# 2_Smoke_detector.net
KiCad netlist of a schematic drawn in Altium Designer
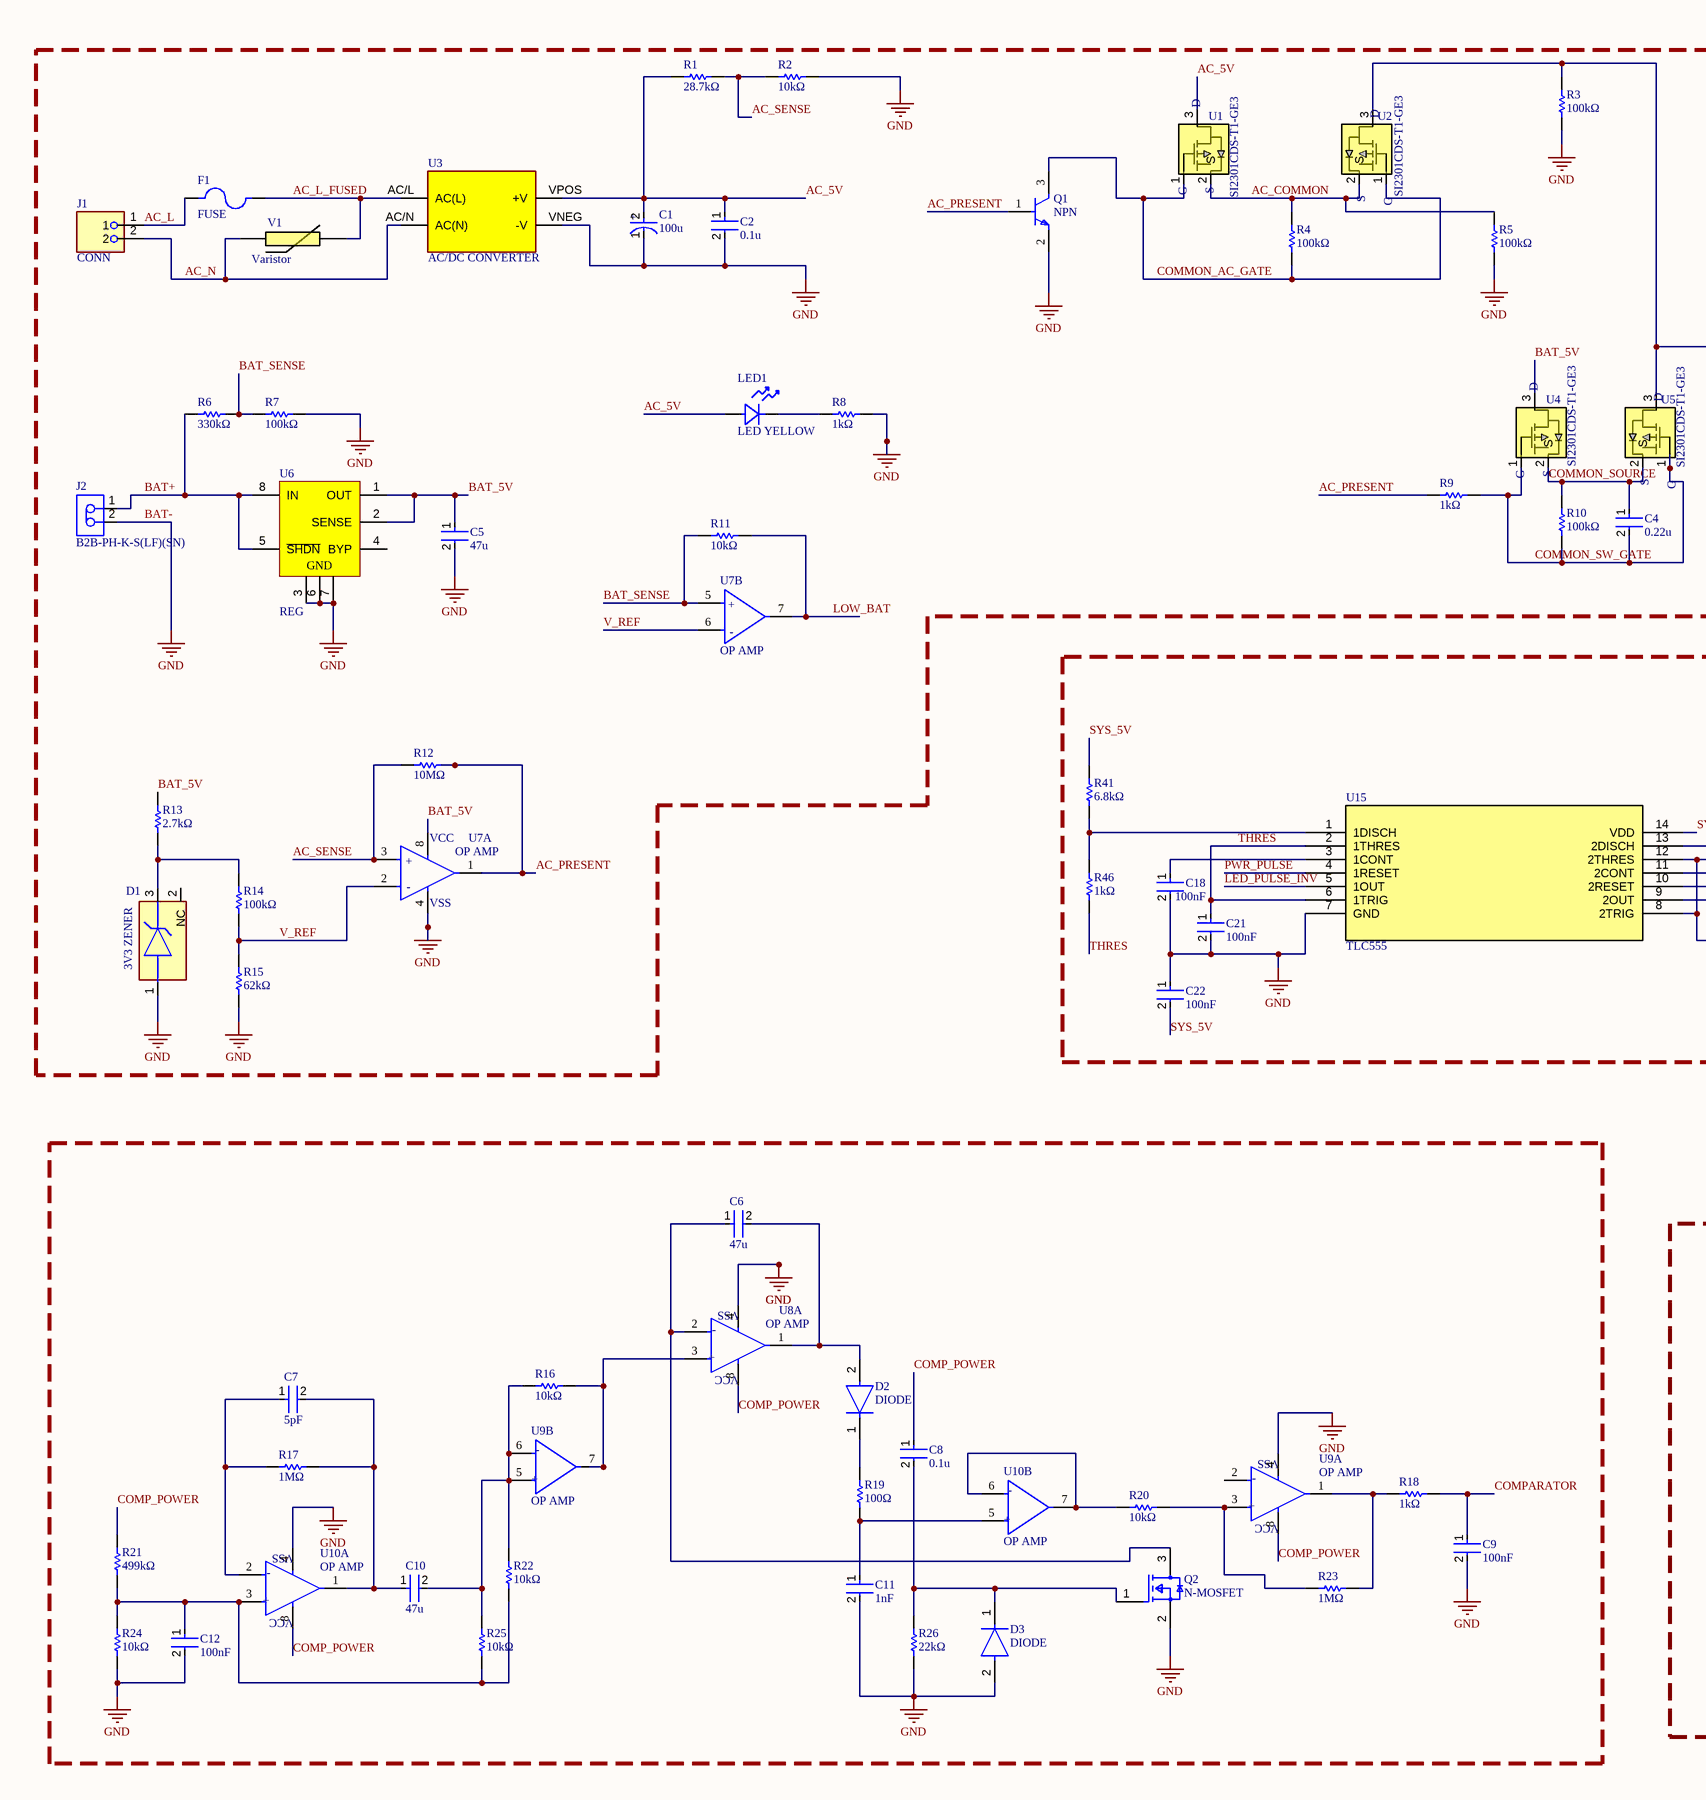
[diagram p0: 2_Smoke_detector.SchDoc, left]
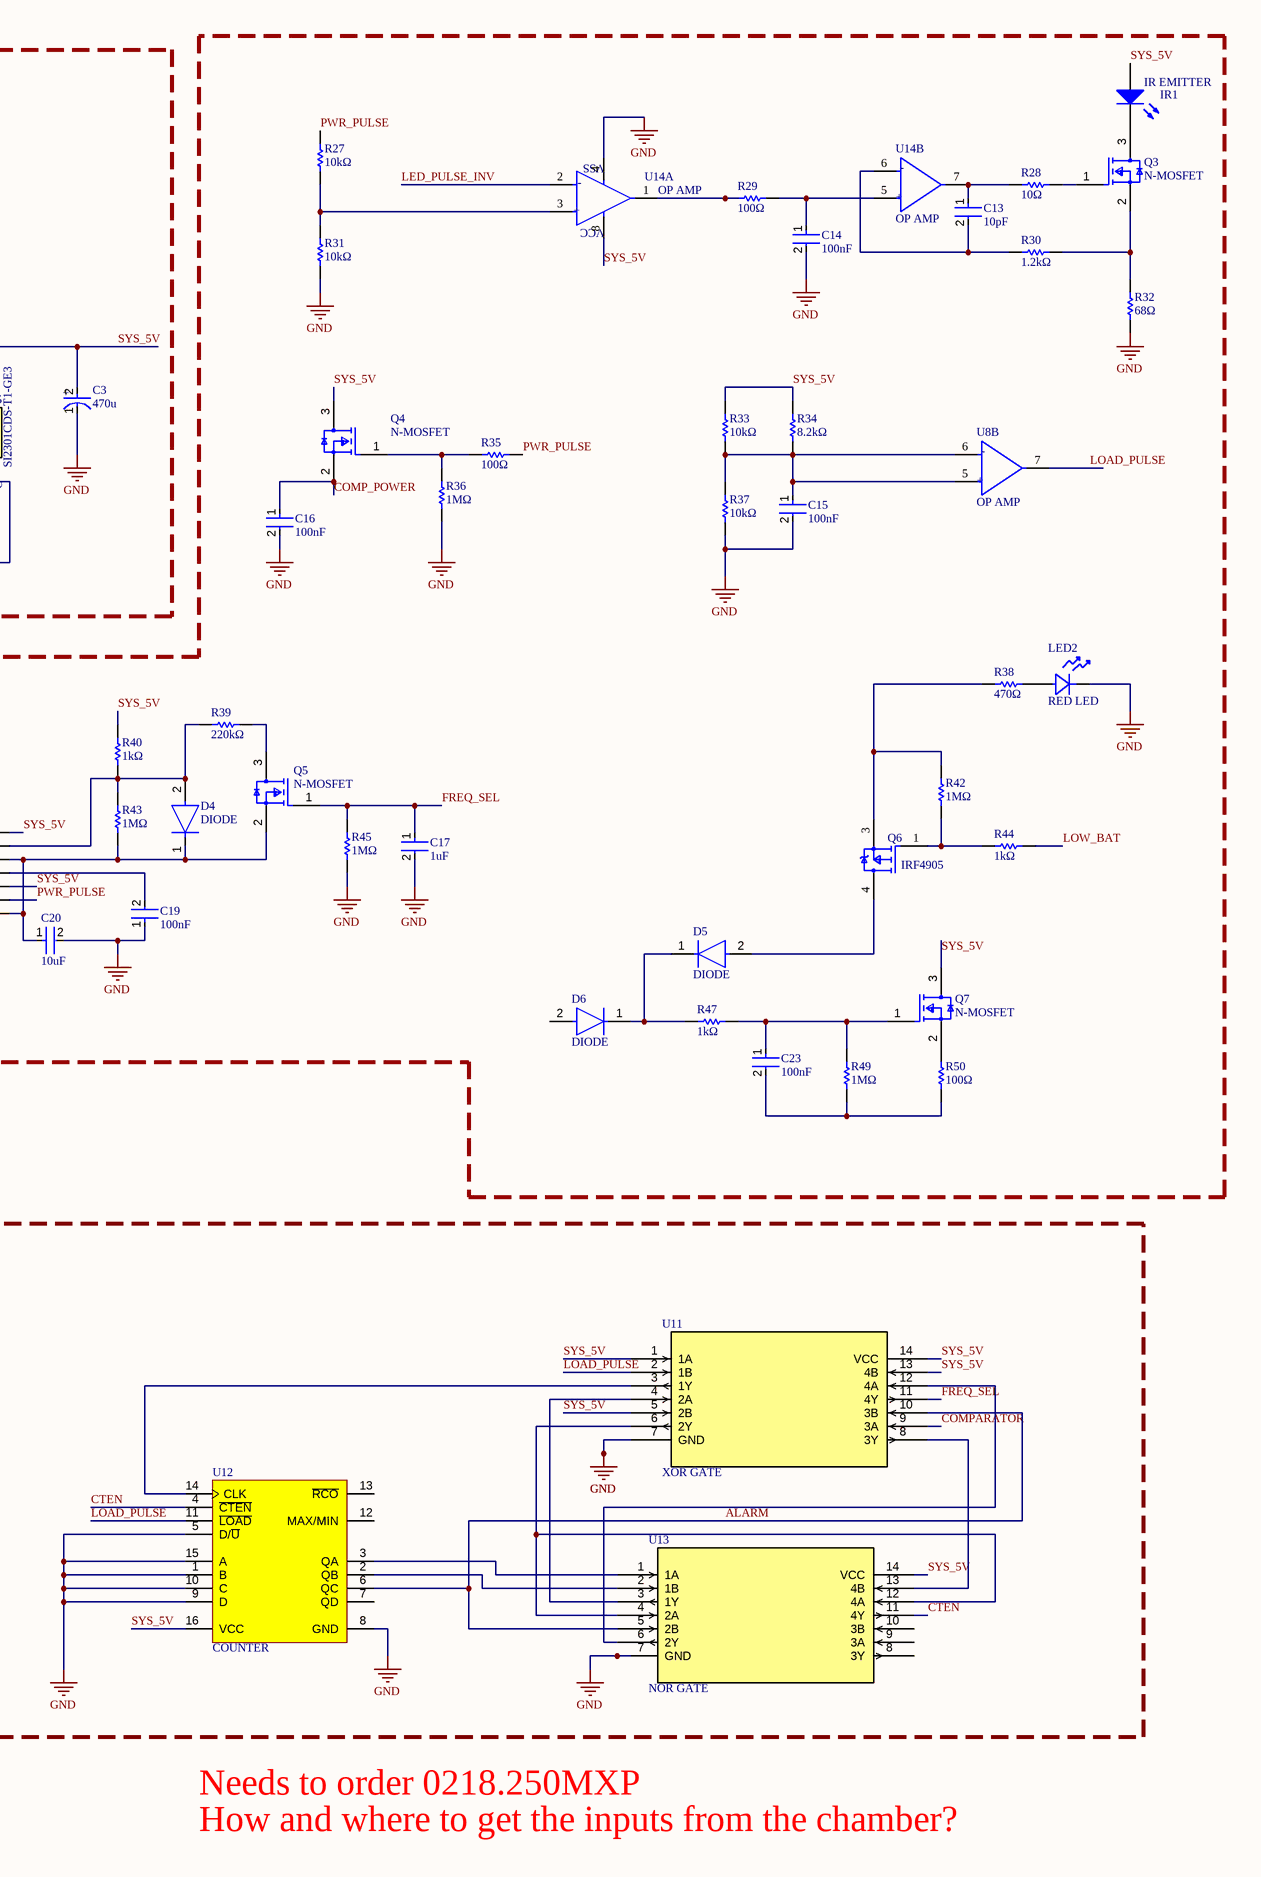
[diagram p1: 2_Smoke_detector.SchDoc, right]

(export (version "E")
  (design (tool "Eeschema 10.0.6"))
  (components
    (comp (ref "C1")
      (value "100u")
      (footprint "CAP_100u")
      (description "CAP ALUM 100uF 20% 16V SMD")
      (fields (field (name "TOLERANCE") "20%") (field (name "VOLTAGE") "16V"))
      (libsource (lib "2_Smoke_Detector") (part "EEEFT1C101AR"))
    )
    (comp (ref "C2")
      (value "0.1u")
      (footprint "0805_CER_CAP")
      (description "CAP CER 0.1uF 50V X7R 0805")
      (fields (field (name "TOLERANCE") "10%") (field (name "VOLTAGE") "50V"))
      (libsource (lib "2_Smoke_Detector") (part "CL21B104KBCNNNC"))
    )
    (comp (ref "C3")
      (value "470u")
      (footprint "Radial_SMD_CAP")
      (description "CAP ALUM 470uF ±20% 10V SMD")
      (fields
        (field (name "MANUFACTURER") "Panasonic")
        (field (name "MANUFACTURER PART NUMBER") "EEEFK1A471P")
      )
      (libsource (lib "2_Smoke_Detector") (part "EEEFK1A471P"))
    )
    (comp (ref "C4")
      (value "0.22u")
      (footprint "0805_CER_CAP")
      (description "CAP CER 0.22uF 10V X7R 0805")
      (fields
        (field (name "MANUFACTURER") "Yageo Group")
        (field (name "MANUFACTURER PART NUMBER") "CC0805KRX7R6BB224")
      )
      (libsource (lib "2_Smoke_Detector") (part "CC0805KRX7R6BB224"))
    )
    (comp (ref "C5")
      (value "47u")
      (footprint "0805_CER_CAP")
      (description "CAP CER 47uF 10V X5R 0805")
      (fields
        (field (name "MANUFACTURER") "Murata")
        (field (name "MANUFACTURER PART NUMBER") "GRM21BR61A476ME15L")
      )
      (libsource (lib "2_Smoke_Detector") (part "GRM21BR61A476ME15L"))
    )
    (comp (ref "C6")
      (value "47u")
      (footprint "0805_CER_CAP")
      (description "CAP CER 47uF 10V X5R 0805")
      (fields
        (field (name "MANUFACTURER") "Murata")
        (field (name "MANUFACTURER PART NUMBER") "GRM21BR61A476ME15L")
      )
      (libsource (lib "2_Smoke_Detector") (part "GRM21BR61A476ME15L"))
    )
    (comp (ref "C7")
      (value "5pF")
      (footprint "0805_CER_CAP")
      (description "CAP CER 5pF 50V NP0 0805")
      (fields
        (field (name "MANUFACTURER") "Yageo Group")
        (field (name "MANUFACTURER PART NUMBER") "CC0805CRNPO9BN5R0")
      )
      (libsource (lib "2_Smoke_Detector") (part "CC0805CRNPO9BN5R0"))
    )
    (comp (ref "C8")
      (value "0.1u")
      (footprint "0805_CER_CAP")
      (description "CAP CER 0.1uF 50V X7R 0805")
      (fields (field (name "TOLERANCE") "10%") (field (name "VOLTAGE") "50V"))
      (libsource (lib "2_Smoke_Detector") (part "CL21B104KBCNNNC"))
    )
    (comp (ref "C9")
      (value "100nF")
      (footprint "0805_CER_CAP")
      (description "CAP CER 100nF 50V X7R 0805")
      (fields
        (field (name "MANUFACTURER") "Yageo Group")
        (field (name "MANUFACTURER PART NUMBER") "CC0805KRX7R9BB104")
      )
      (libsource (lib "2_Smoke_Detector") (part "CC0805KRX7R9BB104"))
    )
    (comp (ref "C10")
      (value "47u")
      (footprint "0805_CER_CAP")
      (description "CAP CER 47uF 10V X5R 0805")
      (fields
        (field (name "MANUFACTURER") "Murata")
        (field (name "MANUFACTURER PART NUMBER") "GRM21BR61A476ME15L")
      )
      (libsource (lib "2_Smoke_Detector") (part "GRM21BR61A476ME15L"))
    )
    (comp (ref "C11")
      (value "1nF")
      (footprint "0805_CER_CAP")
      (description "CAP CER 1nF 50V X7R 0805")
      (fields
        (field (name "MANUFACTURER") "Samsung Electro-Mechanics")
        (field (name "MANUFACTURER PART NUMBER") "CL21B102KBCNNNC")
      )
      (libsource (lib "2_Smoke_Detector") (part "CL21B102KBCNNNC"))
    )
    (comp (ref "C12")
      (value "100nF")
      (footprint "0805_CER_CAP")
      (description "CAP CER 100nF 50V X7R 0805")
      (fields
        (field (name "MANUFACTURER") "Yageo Group")
        (field (name "MANUFACTURER PART NUMBER") "CC0805KRX7R9BB104")
      )
      (libsource (lib "2_Smoke_Detector") (part "CC0805KRX7R9BB104"))
    )
    (comp (ref "C13")
      (value "10pF")
      (footprint "0805_CER_CAP")
      (description "CAP CER 10pF 50V NP0 0805")
      (fields
        (field (name "MANUFACTURER") "Yageo Group")
        (field (name "MANUFACTURER PART NUMBER") "CC0805JRNPO9BN100")
      )
      (libsource (lib "2_Smoke_Detector") (part "CC0805JRNPO9BN100"))
    )
    (comp (ref "C14")
      (value "100nF")
      (footprint "0805_CER_CAP")
      (description "CAP CER 100nF 50V X7R 0805")
      (fields
        (field (name "MANUFACTURER") "Yageo Group")
        (field (name "MANUFACTURER PART NUMBER") "CC0805KRX7R9BB104")
      )
      (libsource (lib "2_Smoke_Detector") (part "CC0805KRX7R9BB104"))
    )
    (comp (ref "C15")
      (value "100nF")
      (footprint "0805_CER_CAP")
      (description "CAP CER 100nF 50V X7R 0805")
      (fields
        (field (name "MANUFACTURER") "Yageo Group")
        (field (name "MANUFACTURER PART NUMBER") "CC0805KRX7R9BB104")
      )
      (libsource (lib "2_Smoke_Detector") (part "CC0805KRX7R9BB104"))
    )
    (comp (ref "C16")
      (value "100nF")
      (footprint "0805_CER_CAP")
      (description "CAP CER 100nF 50V X7R 0805")
      (fields
        (field (name "MANUFACTURER") "Yageo Group")
        (field (name "MANUFACTURER PART NUMBER") "CC0805KRX7R9BB104")
      )
      (libsource (lib "2_Smoke_Detector") (part "CC0805KRX7R9BB104"))
    )
    (comp (ref "C17")
      (value "1uF")
      (footprint "0805_CER_CAP")
      (description "CAP CER 1uF 50V X7R 0805")
      (fields
        (field (name "MANUFACTURER") "Samsung Electro-Mechanics")
        (field (name "MANUFACTURER PART NUMBER") "CL21B105KBFNNNE")
      )
      (libsource (lib "2_Smoke_Detector") (part "CL21B105KBFNNNE"))
    )
    (comp (ref "C18")
      (value "100nF")
      (footprint "0805_CER_CAP")
      (description "CAP CER 100nF 50V X7R 0805")
      (fields
        (field (name "MANUFACTURER") "Yageo Group")
        (field (name "MANUFACTURER PART NUMBER") "CC0805KRX7R9BB104")
      )
      (libsource (lib "2_Smoke_Detector") (part "CC0805KRX7R9BB104"))
    )
    (comp (ref "C19")
      (value "100nF")
      (footprint "0805_CER_CAP")
      (description "CAP CER 100nF 50V X7R 0805")
      (fields
        (field (name "MANUFACTURER") "Yageo Group")
        (field (name "MANUFACTURER PART NUMBER") "CC0805KRX7R9BB104")
      )
      (libsource (lib "2_Smoke_Detector") (part "CC0805KRX7R9BB104"))
    )
    (comp (ref "C20")
      (value "10uF")
      (footprint "0805_CER_CAP")
      (description "CAP CER 10uF 25V X5R 0805")
      (fields
        (field (name "MANUFACTURER") "TAIYO YUDEN")
        (field (name "MANUFACTURER PART NUMBER") "TMK212BBJ106KG-T")
      )
      (libsource (lib "2_Smoke_Detector") (part "TMK212BBJ106KG-T"))
    )
    (comp (ref "C21")
      (value "100nF")
      (footprint "0805_CER_CAP")
      (description "CAP CER 100nF 50V X7R 0805")
      (fields
        (field (name "MANUFACTURER") "Yageo Group")
        (field (name "MANUFACTURER PART NUMBER") "CC0805KRX7R9BB104")
      )
      (libsource (lib "2_Smoke_Detector") (part "CC0805KRX7R9BB104"))
    )
    (comp (ref "C22")
      (value "100nF")
      (footprint "0805_CER_CAP")
      (description "CAP CER 100nF 50V X7R 0805")
      (fields
        (field (name "MANUFACTURER") "Yageo Group")
        (field (name "MANUFACTURER PART NUMBER") "CC0805KRX7R9BB104")
      )
      (libsource (lib "2_Smoke_Detector") (part "CC0805KRX7R9BB104"))
    )
    (comp (ref "C23")
      (value "100nF")
      (footprint "0805_CER_CAP")
      (description "CAP CER 100nF 50V X7R 0805")
      (fields
        (field (name "MANUFACTURER") "Yageo Group")
        (field (name "MANUFACTURER PART NUMBER") "CC0805KRX7R9BB104")
      )
      (libsource (lib "2_Smoke_Detector") (part "CC0805KRX7R9BB104"))
    )
    (comp (ref "D1")
      (value "3V3 ZENER")
      (footprint "FP-SOT23-IPC_B_ZENER")
      (description "DIODE ZENER 3.3V 250MW TO236AB")
      (fields
        (field (name "MANUFACTURER") "Nexperia")
        (field (name "MANUFACTURER PART NUMBER") "BZX84-C3V3,215")
      )
      (libsource (lib "2_Smoke_Detector") (part "BZX84-C3V3,215"))
    )
    (comp (ref "D2")
      (value "DIODE")
      (footprint "FP-477AB-IPC_B")
      (description "DIODE STANDARD 75V 150MA SOD323F")
      (fields (field (name "MANUFACTURER") "onsemi") (field (name "MANUFACTURER PART NUMBER") "1N4148WS"))
      (libsource (lib "2_Smoke_Detector") (part "1N4148WS-E3-08"))
    )
    (comp (ref "D3")
      (value "DIODE")
      (footprint "FP-477AB-IPC_B")
      (description "DIODE STANDARD 75V 150MA SOD323F")
      (fields (field (name "MANUFACTURER") "onsemi") (field (name "MANUFACTURER PART NUMBER") "1N4148WS"))
      (libsource (lib "2_Smoke_Detector") (part "1N4148WS-E3-08"))
    )
    (comp (ref "D4")
      (value "DIODE")
      (footprint "FP-477AB-IPC_B")
      (description "DIODE STANDARD 75V 150MA SOD323F")
      (fields (field (name "MANUFACTURER") "onsemi") (field (name "MANUFACTURER PART NUMBER") "1N4148WS"))
      (libsource (lib "2_Smoke_Detector") (part "1N4148WS-E3-08"))
    )
    (comp (ref "D5")
      (value "DIODE")
      (footprint "FP-477AB-IPC_B")
      (description "DIODE STANDARD 75V 150MA SOD323F")
      (fields (field (name "MANUFACTURER") "onsemi") (field (name "MANUFACTURER PART NUMBER") "1N4148WS"))
      (libsource (lib "2_Smoke_Detector") (part "1N4148WS-E3-08"))
    )
    (comp (ref "D6")
      (value "DIODE")
      (footprint "FP-477AB-IPC_B")
      (description "DIODE STANDARD 75V 150MA SOD323F")
      (fields (field (name "MANUFACTURER") "onsemi") (field (name "MANUFACTURER PART NUMBER") "1N4148WS"))
      (libsource (lib "2_Smoke_Detector") (part "1N4148WS-E3-08"))
    )
    (comp (ref "F1")
      (value "FUSE")
      (footprint "FUSE_4628")
      (description "FUSE HLDR CARTRIDGE 250V 5A PCB")
      (fields (field (name "MANUFACTURER") "Keystone") (field (name "MANUFACTURER PART NUMBER") "4628"))
      (libsource (lib "2_Smoke_Detector") (part "4628"))
    )
    (comp (ref "IR1")
      (value "IR EMITTER")
      (footprint "VISH-TSAL6200")
      (description "EMITTER IR 940NM 100MA RADIAL")
      (fields (field (name "MANUFACTURER") "Vishay") (field (name "MANUFACTURER PART NUMBER") "TSAL6200"))
      (libsource (lib "2_Smoke_Detector") (part "TSAL6200"))
    )
    (comp (ref "J1")
      (value "CONN")
      (footprint "CONN_1715721_PXC")
      (description "TERM BLK 2P SIDE ENT 5.08MM PCB")
      (fields
        (field (name "MANUFACTURER") "Phoenix Contact")
        (field (name "MANUFACTURER PART NUMBER") "1715721")
      )
      (libsource (lib "2_Smoke_Detector") (part "1715721"))
    )
    (comp (ref "J2")
      (value "B2B-PH-K-S(LF)(SN)")
      (footprint "JST")
      (description "CONN HEADER VERT 2POS 2MM")
      (fields (field (name "MANUFACTURER") "JST") (field (name "LCSC PART NUMBER") "C131337"))
      (libsource (lib "2_Smoke_Detector") (part "B2B-PH-K-S(LF)(SN)"))
    )
    (comp (ref "LED1")
      (value "LED YELLOW")
      (footprint "LED_XL-2012SURC_XLG")
      (description "CHIP LED 0805 YELLOW SMD")
      (fields
        (field (name "MANUFACTURER_PART_NUMBER") "XL-2012SURC")
        (field (name "LCSC PART NUMBER") "C965814")
        (field (name "COPYRIGHT") "Copyright (C) 2025 Ultra Librarian. All rights reserved.")
      )
      (libsource (lib "2_Smoke_Detector") (part "XL-2012SURC_YELLOW"))
    )
    (comp (ref "LED2")
      (value "RED LED")
      (footprint "LED_XL-2012SURC_XLG-L")
      (description "CHIP LED 0805 RED SMD")
      (fields
        (field (name "MANUFACTURER_PART_NUMBER") "XL-2012SURC")
        (field (name "LCSC PART NUMBER") "C965812")
        (field (name "COPYRIGHT") "Copyright (C) 2025 Ultra Librarian. All rights reserved.")
      )
      (libsource (lib "2_Smoke_Detector") (part "XL-2012SURC_RED"))
    )
    (comp (ref "Q1")
      (value "NPN")
      (footprint "FP-SOT323-IPC_B")
      (description "TRANS NPN 45V 0.1A SOT-323")
      (fields
        (field (name "MANUFACTURER") "Nexperia")
        (field (name "MANUFACTURER PART NUMBER") "BC847BW,115")
      )
      (libsource (lib "2_Smoke_Detector") (part "BC847BW,115"))
    )
    (comp (ref "Q2")
      (value "N-MOSFET")
      (footprint "SOT23_TOS")
      (description "MOSFET N-CH 30V 5.7A SOT23-3L")
      (fields
        (field (name "MANUFACTURER") "Alpha & Omega Semiconductor")
        (field (name "MANUFACTURER PART NUMBER") "AO3400A")
      )
      (libsource (lib "2_Smoke_Detector") (part "AO3400A"))
    )
    (comp (ref "Q3")
      (value "N-MOSFET")
      (footprint "SOT23_TOS")
      (description "MOSFET N-CH 30V 5.7A SOT23-3L")
      (fields
        (field (name "MANUFACTURER") "Alpha & Omega Semiconductor")
        (field (name "MANUFACTURER PART NUMBER") "AO3400A")
      )
      (libsource (lib "2_Smoke_Detector") (part "AO3400A"))
    )
    (comp (ref "Q4")
      (value "N-MOSFET")
      (footprint "SOT23_TOS")
      (description "MOSFET N-CH 30V 5.7A SOT23-3L")
      (fields
        (field (name "MANUFACTURER") "Alpha & Omega Semiconductor")
        (field (name "MANUFACTURER PART NUMBER") "AO3400A")
      )
      (libsource (lib "2_Smoke_Detector") (part "AO3400A"))
    )
    (comp (ref "Q5")
      (value "N-MOSFET")
      (footprint "SOT23_TOS")
      (description "MOSFET N-CH 30V 5.7A SOT23-3L")
      (fields
        (field (name "MANUFACTURER") "Alpha & Omega Semiconductor")
        (field (name "MANUFACTURER PART NUMBER") "AO3400A")
      )
      (libsource (lib "2_Smoke_Detector") (part "AO3400A"))
    )
    (comp (ref "Q6")
      (value "IRF4905")
      (footprint "FP-PG-TO263-3-MFG")
      (description "MOSFET P-CH 55V 42A D2PAK")
      (fields
        (field (name "MANUFACTURER") "Infineon")
        (field (name "MANUFACTURER PART NUMBER") "IRF4905STRLPBF")
      )
      (libsource (lib "2_Smoke_Detector") (part "IRF4905STRLPBF"))
    )
    (comp (ref "Q7")
      (value "N-MOSFET")
      (footprint "SOT23_TOS")
      (description "MOSFET N-CH 30V 5.7A SOT23-3L")
      (fields
        (field (name "MANUFACTURER") "Alpha & Omega Semiconductor")
        (field (name "MANUFACTURER PART NUMBER") "AO3400A")
      )
      (libsource (lib "2_Smoke_Detector") (part "AO3400A"))
    )
    (comp (ref "R1")
      (value "28.7kΩ")
      (footprint "0805_RES")
      (description "RES 28.7kΩ 0.1% 1/8W 0805")
      (fields
        (field (name "MANUFACTURER") "Yageo Group")
        (field (name "MANUFACTURER PART NUMBER") "RT0805BRD0728K7L")
      )
      (libsource (lib "2_Smoke_Detector") (part "RT0805BRD0728K7L"))
    )
    (comp (ref "R2")
      (value "10kΩ")
      (footprint "0805_RES")
      (description "RES 10kΩ 1% 1/8W 0805")
      (fields
        (field (name "MANUFACTURER") "Vishay")
        (field (name "MANUFACTURER PART NUMBER") "CRCW080510K0FKEA")
      )
      (libsource (lib "2_Smoke_Detector") (part "CRCW080510K0FKEA"))
    )
    (comp (ref "R3")
      (value "100kΩ")
      (footprint "0805_RES")
      (description "RES 100kΩ 1% 1/8W 0805")
      (fields (field (name "TOLERANCE") "1%") (field (name "LCSC PART NUMBER") "C844935"))
      (libsource (lib "2_Smoke_Detector") (part "CRCW0805100KFKEA"))
    )
    (comp (ref "R4")
      (value "100kΩ")
      (footprint "0805_RES")
      (description "RES 100kΩ 1% 1/8W 0805")
      (fields (field (name "TOLERANCE") "1%") (field (name "LCSC PART NUMBER") "C844935"))
      (libsource (lib "2_Smoke_Detector") (part "CRCW0805100KFKEA"))
    )
    (comp (ref "R5")
      (value "100kΩ")
      (footprint "0805_RES")
      (description "RES 100kΩ 1% 1/8W 0805")
      (fields (field (name "TOLERANCE") "1%") (field (name "LCSC PART NUMBER") "C844935"))
      (libsource (lib "2_Smoke_Detector") (part "CRCW0805100KFKEA"))
    )
    (comp (ref "R6")
      (value "330kΩ")
      (footprint "0805_RES")
      (description "RES 330kΩ 1% 1/8W 0805")
      (fields
        (field (name "MANUFACTURER") "Yageo Group")
        (field (name "MANUFACTURER PART NUMBER") "RC0805FR-07330KL")
      )
      (libsource (lib "2_Smoke_Detector") (part "RC0805FR-07330KL"))
    )
    (comp (ref "R7")
      (value "100kΩ")
      (footprint "0805_RES")
      (description "RES 100kΩ 1% 1/8W 0805")
      (fields (field (name "TOLERANCE") "1%") (field (name "LCSC PART NUMBER") "C844935"))
      (libsource (lib "2_Smoke_Detector") (part "CRCW0805100KFKEA"))
    )
    (comp (ref "R8")
      (value "1kΩ")
      (footprint "0805_RES")
      (description "RES 1kΩ 1% 1/8W 0805")
      (fields (field (name "PART NUMBER") "CRCW08051K00FKEA") (field (name "MANUFACTURER") "Vishay Dale"))
      (libsource (lib "2_Smoke_Detector") (part "CRCW08051K00FKEA"))
    )
    (comp (ref "R9")
      (value "1kΩ")
      (footprint "0805_RES")
      (description "RES 1kΩ 1% 1/8W 0805")
      (fields (field (name "PART NUMBER") "CRCW08051K00FKEA") (field (name "MANUFACTURER") "Vishay Dale"))
      (libsource (lib "2_Smoke_Detector") (part "CRCW08051K00FKEA"))
    )
    (comp (ref "R10")
      (value "100kΩ")
      (footprint "0805_RES")
      (description "RES 100kΩ 1% 1/8W 0805")
      (fields (field (name "TOLERANCE") "1%") (field (name "LCSC PART NUMBER") "C844935"))
      (libsource (lib "2_Smoke_Detector") (part "CRCW0805100KFKEA"))
    )
    (comp (ref "R11")
      (value "10kΩ")
      (footprint "0805_RES")
      (description "RES 10kΩ 1% 1/8W 0805")
      (fields
        (field (name "MANUFACTURER") "Vishay")
        (field (name "MANUFACTURER PART NUMBER") "CRCW080510K0FKEA")
      )
      (libsource (lib "2_Smoke_Detector") (part "CRCW080510K0FKEA"))
    )
    (comp (ref "R12")
      (value "10MΩ")
      (footprint "0805_RES")
      (description "RES 10MΩ 1% 1/8W 0805")
      (fields
        (field (name "MANUFACTURER") "Vishay")
        (field (name "MANUFACTURER PART NUMBER") "CRCW080510M0FKEA")
      )
      (libsource (lib "2_Smoke_Detector") (part "CRCW080510M0FKEA"))
    )
    (comp (ref "R13")
      (value "2.7kΩ")
      (footprint "0805_RES")
      (description "RES 2.7kΩ 1% 1/8W 0805")
      (fields (field (name "TOLERANCE") "1%") (field (name "LCSC PART NUMBER") "C844836"))
      (libsource (lib "2_Smoke_Detector") (part "CRCW08052K70FKEA"))
    )
    (comp (ref "R14")
      (value "100kΩ")
      (footprint "0805_RES")
      (description "RES 100kΩ 1% 1/8W 0805")
      (fields (field (name "TOLERANCE") "1%") (field (name "LCSC PART NUMBER") "C844935"))
      (libsource (lib "2_Smoke_Detector") (part "CRCW0805100KFKEA"))
    )
    (comp (ref "R15")
      (value "62kΩ")
      (footprint "0805_RES")
      (description "RES 62kΩ 1% 1/8W 0805")
      (fields
        (field (name "MANUFACTURER") "Vishay")
        (field (name "MANUFACTURER PART NUMBER") "CRCW080562K0FKEA")
      )
      (libsource (lib "2_Smoke_Detector") (part "CRCW080562K0FKEA"))
    )
    (comp (ref "R16")
      (value "10kΩ")
      (footprint "0805_RES")
      (description "RES 10kΩ 1% 1/8W 0805")
      (fields
        (field (name "MANUFACTURER") "Vishay")
        (field (name "MANUFACTURER PART NUMBER") "CRCW080510K0FKEA")
      )
      (libsource (lib "2_Smoke_Detector") (part "CRCW080510K0FKEA"))
    )
    (comp (ref "R17")
      (value "1MΩ")
      (footprint "0805_RES")
      (description "RES 1MΩ ±1% 125mW 0805")
      (fields
        (field (name "MANUFACTURER") "Yageo Group")
        (field (name "MANUFACTURER PART NUMBER") "RC0805FR-071ML")
      )
      (libsource (lib "2_Smoke_Detector") (part "RC0805FR-071ML"))
    )
    (comp (ref "R18")
      (value "1kΩ")
      (footprint "0805_RES")
      (description "RES 1kΩ 1% 1/8W 0805")
      (fields (field (name "PART NUMBER") "CRCW08051K00FKEA") (field (name "MANUFACTURER") "Vishay Dale"))
      (libsource (lib "2_Smoke_Detector") (part "CRCW08051K00FKEA"))
    )
    (comp (ref "R19")
      (value "100Ω")
      (footprint "0805_RES")
      (description "RES 100Ω ±1% 125mW 0805")
      (fields
        (field (name "MANUFACTURER") "Vishay")
        (field (name "MANUFACTURER PART NUMBER") "CRCW0805100RFKEA")
      )
      (libsource (lib "2_Smoke_Detector") (part "CRCW0805100RFKEA"))
    )
    (comp (ref "R20")
      (value "10kΩ")
      (footprint "0805_RES")
      (description "RES 10kΩ 1% 1/8W 0805")
      (fields
        (field (name "MANUFACTURER") "Vishay")
        (field (name "MANUFACTURER PART NUMBER") "CRCW080510K0FKEA")
      )
      (libsource (lib "2_Smoke_Detector") (part "CRCW080510K0FKEA"))
    )
    (comp (ref "R21")
      (value "499kΩ")
      (footprint "0805_RES")
      (description "RES 499kΩ ±1% 125mW 0805")
      (fields
        (field (name "MANUFACTURER") "Yageo Group")
        (field (name "MANUFACTURER PART NUMBER") "RC0805FR-07499KL")
      )
      (libsource (lib "2_Smoke_Detector") (part "RC0805FR-07499KL"))
    )
    (comp (ref "R22")
      (value "10kΩ")
      (footprint "0805_RES")
      (description "RES 10kΩ 1% 1/8W 0805")
      (fields
        (field (name "MANUFACTURER") "Vishay")
        (field (name "MANUFACTURER PART NUMBER") "CRCW080510K0FKEA")
      )
      (libsource (lib "2_Smoke_Detector") (part "CRCW080510K0FKEA"))
    )
    (comp (ref "R23")
      (value "1MΩ")
      (footprint "0805_RES")
      (description "RES 1MΩ ±1% 125mW 0805")
      (fields
        (field (name "MANUFACTURER") "Yageo Group")
        (field (name "MANUFACTURER PART NUMBER") "RC0805FR-071ML")
      )
      (libsource (lib "2_Smoke_Detector") (part "RC0805FR-071ML"))
    )
    (comp (ref "R24")
      (value "10kΩ")
      (footprint "0805_RES")
      (description "RES 10kΩ 1% 1/8W 0805")
      (fields
        (field (name "MANUFACTURER") "Vishay")
        (field (name "MANUFACTURER PART NUMBER") "CRCW080510K0FKEA")
      )
      (libsource (lib "2_Smoke_Detector") (part "CRCW080510K0FKEA"))
    )
    (comp (ref "R25")
      (value "10kΩ")
      (footprint "0805_RES")
      (description "RES 10kΩ 1% 1/8W 0805")
      (fields
        (field (name "MANUFACTURER") "Vishay")
        (field (name "MANUFACTURER PART NUMBER") "CRCW080510K0FKEA")
      )
      (libsource (lib "2_Smoke_Detector") (part "CRCW080510K0FKEA"))
    )
    (comp (ref "R26")
      (value "22kΩ")
      (footprint "0805_RES")
      (description "RES 22kΩ 1% 1/8W 0805")
      (fields
        (field (name "MANUFACTURER") "Vishay")
        (field (name "MANUFACTURER PART NUMBER") "CRCW080522K0FKEAC")
      )
      (libsource (lib "2_Smoke_Detector") (part "CRCW080522K0FKEAC"))
    )
    (comp (ref "R27")
      (value "10kΩ")
      (footprint "0805_RES")
      (description "RES 10kΩ 1% 1/8W 0805")
      (fields
        (field (name "MANUFACTURER") "Vishay")
        (field (name "MANUFACTURER PART NUMBER") "CRCW080510K0FKEA")
      )
      (libsource (lib "2_Smoke_Detector") (part "CRCW080510K0FKEA"))
    )
    (comp (ref "R28")
      (value "10Ω")
      (footprint "0805_RES")
      (description "RES 10Ω ±1% 125mW 0805")
      (fields
        (field (name "MANUFACTURER") "Vishay")
        (field (name "MANUFACTURER PART NUMBER") "CRCW080510R0FKEA")
      )
      (libsource (lib "2_Smoke_Detector") (part "CRCW080510R0FKEA"))
    )
    (comp (ref "R29")
      (value "100Ω")
      (footprint "0805_RES")
      (description "RES 100Ω ±1% 125mW 0805")
      (fields
        (field (name "MANUFACTURER") "Vishay")
        (field (name "MANUFACTURER PART NUMBER") "CRCW0805100RFKEA")
      )
      (libsource (lib "2_Smoke_Detector") (part "CRCW0805100RFKEA"))
    )
    (comp (ref "R30")
      (value "1.2kΩ")
      (footprint "0805_RES")
      (description "RES 1.2kΩ ±5% 125mW 0805")
      (fields (field (name "LCSC PART NUMBER") "C2933520"))
      (libsource (lib "2_Smoke_Detector") (part "FRC0805J122 TS"))
    )
    (comp (ref "R31")
      (value "10kΩ")
      (footprint "0805_RES")
      (description "RES 10kΩ 1% 1/8W 0805")
      (fields
        (field (name "MANUFACTURER") "Vishay")
        (field (name "MANUFACTURER PART NUMBER") "CRCW080510K0FKEA")
      )
      (libsource (lib "2_Smoke_Detector") (part "CRCW080510K0FKEA"))
    )
    (comp (ref "R32")
      (value "68Ω")
      (footprint "0805_RES")
      (description "RES 68Ω ±1% 125mW 0805")
      (fields (field (name "LCSC PART NUMBER") "C2933487"))
      (libsource (lib "2_Smoke_Detector") (part "FRC0805F68R0TS"))
    )
    (comp (ref "R33")
      (value "10kΩ")
      (footprint "0805_RES")
      (description "RES 10kΩ 1% 1/8W 0805")
      (fields
        (field (name "MANUFACTURER") "Vishay")
        (field (name "MANUFACTURER PART NUMBER") "CRCW080510K0FKEA")
      )
      (libsource (lib "2_Smoke_Detector") (part "CRCW080510K0FKEA"))
    )
    (comp (ref "R34")
      (value "8.2kΩ")
      (footprint "0805_RES")
      (description "RES 8.2kΩ ±1% 125mW 0805")
      (fields
        (field (name "MANUFACTURER") "Vishay")
        (field (name "MANUFACTURER PART NUMBER") "CRCW08058K20FKEA")
      )
      (libsource (lib "2_Smoke_Detector") (part "CRCW08058K20FKEA"))
    )
    (comp (ref "R35")
      (value "100Ω")
      (footprint "0805_RES")
      (description "RES 100Ω ±1% 125mW 0805")
      (fields
        (field (name "MANUFACTURER") "Vishay")
        (field (name "MANUFACTURER PART NUMBER") "CRCW0805100RFKEA")
      )
      (libsource (lib "2_Smoke_Detector") (part "CRCW0805100RFKEA"))
    )
    (comp (ref "R36")
      (value "1MΩ")
      (footprint "0805_RES")
      (description "RES 1MΩ ±1% 125mW 0805")
      (fields
        (field (name "MANUFACTURER") "Yageo Group")
        (field (name "MANUFACTURER PART NUMBER") "RC0805FR-071ML")
      )
      (libsource (lib "2_Smoke_Detector") (part "RC0805FR-071ML"))
    )
    (comp (ref "R37")
      (value "10kΩ")
      (footprint "0805_RES")
      (description "RES 10kΩ 1% 1/8W 0805")
      (fields
        (field (name "MANUFACTURER") "Vishay")
        (field (name "MANUFACTURER PART NUMBER") "CRCW080510K0FKEA")
      )
      (libsource (lib "2_Smoke_Detector") (part "CRCW080510K0FKEA"))
    )
    (comp (ref "R38")
      (value "470Ω")
      (footprint "0805_RES")
      (description "RES 470Ω 1% 1/8W 0805")
      (fields
        (field (name "MANUFACTURER") "Yageo Group")
        (field (name "MANUFACTURER PART NUMBER") "RC0805FR-07470RL")
      )
      (libsource (lib "2_Smoke_Detector") (part "RC0805FR-07470RL"))
    )
    (comp (ref "R39")
      (value "220kΩ")
      (footprint "0805_RES")
      (description "RES 220kΩ ±1% 125mW 0805")
      (fields (field (name "LCSC PART NUMBER") "C2907242"))
      (libsource (lib "2_Smoke_Detector") (part "FRC0805F2203TS"))
    )
    (comp (ref "R40")
      (value "1kΩ")
      (footprint "0805_RES")
      (description "RES 1kΩ 1% 1/8W 0805")
      (fields (field (name "PART NUMBER") "CRCW08051K00FKEA") (field (name "MANUFACTURER") "Vishay Dale"))
      (libsource (lib "2_Smoke_Detector") (part "CRCW08051K00FKEA"))
    )
    (comp (ref "R41")
      (value "6.8kΩ")
      (footprint "0805_RES")
      (description "RES 6.8kΩ ±1% 125mW 0805")
      (fields (field (name "LCSC PART NUMBER") "C2907276"))
      (libsource (lib "2_Smoke_Detector") (part "FRC0805F6801TS"))
    )
    (comp (ref "R42")
      (value "1MΩ")
      (footprint "0805_RES")
      (description "RES 1MΩ ±1% 125mW 0805")
      (fields
        (field (name "MANUFACTURER") "Yageo Group")
        (field (name "MANUFACTURER PART NUMBER") "RC0805FR-071ML")
      )
      (libsource (lib "2_Smoke_Detector") (part "RC0805FR-071ML"))
    )
    (comp (ref "R43")
      (value "1MΩ")
      (footprint "0805_RES")
      (description "RES 1MΩ ±1% 125mW 0805")
      (fields
        (field (name "MANUFACTURER") "Yageo Group")
        (field (name "MANUFACTURER PART NUMBER") "RC0805FR-071ML")
      )
      (libsource (lib "2_Smoke_Detector") (part "RC0805FR-071ML"))
    )
    (comp (ref "R44")
      (value "1kΩ")
      (footprint "0805_RES")
      (description "RES 1kΩ 1% 1/8W 0805")
      (fields (field (name "PART NUMBER") "CRCW08051K00FKEA") (field (name "MANUFACTURER") "Vishay Dale"))
      (libsource (lib "2_Smoke_Detector") (part "CRCW08051K00FKEA"))
    )
    (comp (ref "R45")
      (value "1MΩ")
      (footprint "0805_RES")
      (description "RES 1MΩ ±1% 125mW 0805")
      (fields
        (field (name "MANUFACTURER") "Yageo Group")
        (field (name "MANUFACTURER PART NUMBER") "RC0805FR-071ML")
      )
      (libsource (lib "2_Smoke_Detector") (part "RC0805FR-071ML"))
    )
    (comp (ref "R46")
      (value "1kΩ")
      (footprint "0805_RES")
      (description "RES 1kΩ 1% 1/8W 0805")
      (fields (field (name "PART NUMBER") "CRCW08051K00FKEA") (field (name "MANUFACTURER") "Vishay Dale"))
      (libsource (lib "2_Smoke_Detector") (part "CRCW08051K00FKEA"))
    )
    (comp (ref "R47")
      (value "1kΩ")
      (footprint "0805_RES")
      (description "RES 1kΩ 1% 1/8W 0805")
      (fields (field (name "PART NUMBER") "CRCW08051K00FKEA") (field (name "MANUFACTURER") "Vishay Dale"))
      (libsource (lib "2_Smoke_Detector") (part "CRCW08051K00FKEA"))
    )
    (comp (ref "R49")
      (value "1MΩ")
      (footprint "0805_RES")
      (description "RES 1MΩ ±1% 125mW 0805")
      (fields
        (field (name "MANUFACTURER") "Yageo Group")
        (field (name "MANUFACTURER PART NUMBER") "RC0805FR-071ML")
      )
      (libsource (lib "2_Smoke_Detector") (part "RC0805FR-071ML"))
    )
    (comp (ref "R50")
      (value "100Ω")
      (footprint "0805_RES")
      (description "RES 100Ω ±1% 125mW 0805")
      (fields
        (field (name "MANUFACTURER") "Vishay")
        (field (name "MANUFACTURER PART NUMBER") "CRCW0805100RFKEA")
      )
      (libsource (lib "2_Smoke_Detector") (part "CRCW0805100RFKEA"))
    )
    (comp (ref "U1")
      (value "SI2301CDS-T1-GE3")
      (footprint "TO-236_VIS")
      (description "MOSFET P-CH 20V 3.1A SOT23-3")
      (fields
        (field (name "LCSC PART NUMBER") "C10487")
        (field (name "COPYRIGHT") "Copyright (C) 2026 Ultra Librarian. All rights reserved.")
      )
      (libsource (lib "2_Smoke_Detector") (part "SI2301CDS-T1-GE3"))
    )
    (comp (ref "U2")
      (value "SI2301CDS-T1-GE3")
      (footprint "TO-236_VIS")
      (description "MOSFET P-CH 20V 3.1A SOT23-3")
      (fields
        (field (name "LCSC PART NUMBER") "C10487")
        (field (name "COPYRIGHT") "Copyright (C) 2026 Ultra Librarian. All rights reserved.")
      )
      (libsource (lib "") (part "SI2301CDS-T1-GE3_1"))
    )
    (comp (ref "U3")
      (value "AC/DC CONVERTER")
      (footprint "Smoke_detector:CONV_IRM-05-5")
      (description "AC/DC CONVERTER 5V 5W")
      (fields (field (name "MANUFACTURER") "Mean Well") (field (name "MANUFACTURER PART NUMBER") "IRM-05-5"))
      (libsource (lib "2_Smoke_Detector") (part "IRM-05-5"))
    )
    (comp (ref "U4")
      (value "SI2301CDS-T1-GE3")
      (footprint "TO-236_VIS")
      (description "MOSFET P-CH 20V 3.1A SOT23-3")
      (fields
        (field (name "LCSC PART NUMBER") "C10487")
        (field (name "COPYRIGHT") "Copyright (C) 2026 Ultra Librarian. All rights reserved.")
      )
      (libsource (lib "2_Smoke_Detector") (part "SI2301CDS-T1-GE3"))
    )
    (comp (ref "U5")
      (value "SI2301CDS-T1-GE3")
      (footprint "TO-236_VIS")
      (description "MOSFET P-CH 20V 3.1A SOT23-3")
      (fields
        (field (name "LCSC PART NUMBER") "C10487")
        (field (name "COPYRIGHT") "Copyright (C) 2026 Ultra Librarian. All rights reserved.")
      )
      (libsource (lib "") (part "SI2301CDS-T1-GE3_1"))
    )
    (comp (ref "U6")
      (value "REG")
      (footprint "SO-8_S_LIT")
      (description "IC REG LINEAR 5V 500MA 8-SO")
      (fields
        (field (name "MANUFACTURER") "Analog Devices")
        (field (name "MANUFACTURER PART NUMBER") "LT1763IS8-5#PBF")
      )
      (libsource (lib "2_Smoke_Detector") (part "LT1763IS8-5#PBF"))
    )
    (comp (ref "U7")
      (value "OP AMP")
      (footprint "IC_TLV9062_8_SOIC")
      (description "IC OP AMP 2CH 8-SOIC")
      (fields (field (name "LCSC PART NUMBER") "C398355"))
      (libsource (lib "2_Smoke_Detector") (part "TLV9062IDR"))
    )
    (comp (ref "U8")
      (value "OP AMP")
      (footprint "IC_TLV9062_8_SOIC")
      (description "IC OP AMP 2CH 8-SOIC")
      (fields (field (name "LCSC PART NUMBER") "C398355"))
      (libsource (lib "2_Smoke_Detector") (part "TLV9062IDR"))
    )
    (comp (ref "U9")
      (value "OP AMP")
      (footprint "IC_TLV9062_8_SOIC")
      (description "IC OP AMP 2CH 8-SOIC")
      (fields (field (name "LCSC PART NUMBER") "C398355"))
      (libsource (lib "2_Smoke_Detector") (part "TLV9062IDR"))
    )
    (comp (ref "U10")
      (value "OP AMP")
      (footprint "IC_TLV9062_8_SOIC")
      (description "IC OP AMP 2CH 8-SOIC")
      (fields (field (name "LCSC PART NUMBER") "C398355"))
      (libsource (lib "2_Smoke_Detector") (part "TLV9062IDR"))
    )
    (comp (ref "U11")
      (value "XOR GATE")
      (footprint "SOT108-1_NXP")
      (description "IC XOR 4-CIR 2-IN 14-SOIC")
      (fields
        (field (name "MANUFACTURER") "Nexperia")
        (field (name "MANUFACTURER PART NUMBER") "74HC86D,653")
      )
      (libsource (lib "2_Smoke_Detector") (part "74HC86D,653"))
    )
    (comp (ref "U12")
      (value "COUNTER")
      (footprint "D0016A_N")
      (description "IC BINARY COUNTER 4-BIT 16SOIC")
      (fields
        (field (name "MANUFACTURER") "Texas Instruments")
        (field (name "MANUFACTURER PART NUMBER") "SN74HC191DR")
      )
      (libsource (lib "2_Smoke_Detector") (part "SN74HC191DR"))
    )
    (comp (ref "U13")
      (value "NOR GATE")
      (footprint "SOT108-1_NXP")
      (description "IC NOR 4-CIR 2-IN 14-SOIC")
      (fields
        (field (name "MANUFACTURER") "Nexperia")
        (field (name "MANUFACTURER PART NUMBER") "74HC02D,653")
      )
      (libsource (lib "2_Smoke_Detector") (part "74HC02D,653"))
    )
    (comp (ref "U14")
      (value "OP AMP")
      (footprint "IC_TLV9062_8_SOIC")
      (description "IC OP AMP 2CH 8-SOIC")
      (fields (field (name "LCSC PART NUMBER") "C398355"))
      (libsource (lib "2_Smoke_Detector") (part "TLV9062IDR"))
    )
    (comp (ref "U15")
      (value "TLC555")
      (footprint "D14")
      (description "IC OSC TIMER DUAL 2.1MHZ 14-SOIC")
      (fields
        (field (name "MANUFACTURER") "Texas Instruments")
        (field (name "MANUFACTURER PART NUMBER") "TLC556IDR")
      )
      (libsource (lib "2_Smoke_Detector") (part "TLC556IDR"))
    )
    (comp (ref "V1")
      (value "Varistor")
      (footprint "LA_14MM_LOW_LTF")
      (description "VARISTOR 430V 4.5KA DISC 14MM")
      (fields
        (field (name "MANUFACTURER_PART_NUMBER") "V275LA20AP")
        (field (name "LCSC PART NUMBER") "C70419")
        (field (name "COPYRIGHT") "Copyright (C) 2025 Ultra Librarian. All rights reserved.")
      )
      (libsource (lib "2_Smoke_Detector") (part "V275LA20AP"))
    )
  )
  (nets
    (net (code "1") (name "/AC_5V") (class "Default")
      (node (ref "C1") (pin "2") (pinfunction "A_2") (pintype "passive"))
      (node (ref "C2") (pin "1") (pinfunction "1_1") (pintype "passive"))
      (node (ref "LED1") (pin "2") (pinfunction "2_2") (pintype "passive"))
      (node (ref "R1") (pin "1") (pinfunction "1_1") (pintype "passive"))
      (node (ref "U1") (pin "3") (pinfunction "D_3") (pintype "passive"))
      (node (ref "U3") (pin "VPOS") (pinfunction "+V_VPOS") (pintype "passive"))
    )
    (net (code "2") (name "/AC_COMMON") (class "Default")
      (node (ref "R4") (pin "2") (pinfunction "2_2") (pintype "passive"))
      (node (ref "R5") (pin "2") (pinfunction "2_2") (pintype "passive"))
      (node (ref "U1") (pin "2") (pinfunction "S_2") (pintype "passive"))
      (node (ref "U2") (pin "2") (pinfunction "S_2") (pintype "passive"))
    )
    (net (code "3") (name "/AC_L") (class "Default")
      (node (ref "F1") (pin "1") (pinfunction "1_1") (pintype "passive"))
      (node (ref "J1") (pin "1") (pinfunction "1_1") (pintype "passive"))
    )
    (net (code "4") (name "/AC_L_FUSED") (class "Default")
      (node (ref "F1") (pin "2") (pinfunction "2_2") (pintype "passive"))
      (node (ref "U3") (pin "AC/L") (pinfunction "AC(L)_AC/L") (pintype "passive"))
      (node (ref "V1") (pin "2") (pinfunction "2_2") (pintype "passive"))
    )
    (net (code "5") (name "/AC_N") (class "Default")
      (node (ref "J1") (pin "2") (pinfunction "2_2") (pintype "passive"))
      (node (ref "U3") (pin "AC/N") (pinfunction "AC(N)_AC/N") (pintype "passive"))
      (node (ref "V1") (pin "1") (pinfunction "1_1") (pintype "passive"))
    )
    (net (code "6") (name "/AC_PRESENT") (class "Default")
      (node (ref "Q1") (pin "1") (pinfunction "B_1") (pintype "passive"))
      (node (ref "R12") (pin "2") (pinfunction "2_2") (pintype "passive"))
      (node (ref "R9") (pin "1") (pinfunction "1_1") (pintype "passive"))
      (node (ref "U7") (pin "1") (pinfunction "OUT1_1") (pintype "passive"))
    )
    (net (code "7") (name "/AC_SENSE") (class "Default")
      (node (ref "R1") (pin "2") (pinfunction "2_2") (pintype "passive"))
      (node (ref "R12") (pin "1") (pinfunction "1_1") (pintype "passive"))
      (node (ref "R2") (pin "1") (pinfunction "1_1") (pintype "passive"))
      (node (ref "U7") (pin "3") (pinfunction "IN1+_3") (pintype "tri_state"))
    )
    (net (code "8") (name "/ALARM") (class "Default")
      (node (ref "U11") (pin "10") (pinfunction "3B_10") (pintype "passive"))
      (node (ref "U12") (pin "6") (pinfunction "QC_6") (pintype "passive"))
      (node (ref "U13") (pin "5") (pinfunction "2B_5") (pintype "passive"))
    )
    (net (code "9") (name "/BAT+") (class "Default")
      (node (ref "J2") (pin "1") (pinfunction "1_1") (pintype "passive"))
      (node (ref "R6") (pin "1") (pinfunction "1_1") (pintype "passive"))
      (node (ref "U6") (pin "5") (pinfunction "~{SHDN}_5") (pintype "passive"))
      (node (ref "U6") (pin "8") (pinfunction "IN_8") (pintype "power_in"))
    )
    (net (code "10") (name "/BAT_5V") (class "Default")
      (node (ref "C5") (pin "1") (pinfunction "1_1") (pintype "passive"))
      (node (ref "R13") (pin "2") (pinfunction "2_2") (pintype "passive"))
      (node (ref "U4") (pin "3") (pinfunction "D_3") (pintype "passive"))
      (node (ref "U6") (pin "1") (pinfunction "OUT_1") (pintype "power_in"))
      (node (ref "U6") (pin "2") (pinfunction "SENSE_2") (pintype "passive"))
      (node (ref "U7") (pin "8") (pinfunction "V+_8") (pintype "power_in"))
    )
    (net (code "11") (name "/BAT_SENSE") (class "Default")
      (node (ref "R11") (pin "1") (pinfunction "1_1") (pintype "passive"))
      (node (ref "R6") (pin "2") (pinfunction "2_2") (pintype "passive"))
      (node (ref "R7") (pin "1") (pinfunction "1_1") (pintype "passive"))
      (node (ref "U7") (pin "5") (pinfunction "IN2+_5") (pintype "tri_state"))
    )
    (net (code "12") (name "/COMMON_AC_GATE") (class "Default")
      (node (ref "Q1") (pin "3") (pinfunction "C_3") (pintype "passive"))
      (node (ref "R4") (pin "1") (pinfunction "1_1") (pintype "passive"))
      (node (ref "U1") (pin "1") (pinfunction "G_1") (pintype "passive"))
      (node (ref "U2") (pin "1") (pinfunction "G_1") (pintype "passive"))
    )
    (net (code "13") (name "/COMMON_SOURCE") (class "Default")
      (node (ref "C4") (pin "1") (pinfunction "1_1") (pintype "passive"))
      (node (ref "R10") (pin "2") (pinfunction "2_2") (pintype "passive"))
      (node (ref "U4") (pin "2") (pinfunction "S_2") (pintype "passive"))
      (node (ref "U5") (pin "2") (pinfunction "S_2") (pintype "passive"))
    )
    (net (code "14") (name "/COMMON_SW_GATE") (class "Default")
      (node (ref "C4") (pin "2") (pinfunction "2_2") (pintype "passive"))
      (node (ref "R10") (pin "1") (pinfunction "1_1") (pintype "passive"))
      (node (ref "R9") (pin "2") (pinfunction "2_2") (pintype "passive"))
      (node (ref "U4") (pin "1") (pinfunction "G_1") (pintype "passive"))
      (node (ref "U5") (pin "1") (pinfunction "G_1") (pintype "passive"))
    )
    (net (code "15") (name "/COMPARATOR") (class "Default")
      (node (ref "C9") (pin "1") (pinfunction "1_1") (pintype "passive"))
      (node (ref "R18") (pin "2") (pinfunction "2_2") (pintype "passive"))
      (node (ref "U11") (pin "9") (pinfunction "3A_9") (pintype "passive"))
    )
    (net (code "16") (name "/COMP_POWER") (class "Default")
      (node (ref "C16") (pin "1") (pinfunction "1_1") (pintype "passive"))
      (node (ref "C8") (pin "1") (pinfunction "1_1") (pintype "passive"))
      (node (ref "Q4") (pin "2") (pinfunction "S_2") (pintype "passive"))
      (node (ref "R21") (pin "2") (pinfunction "2_2") (pintype "passive"))
      (node (ref "U10") (pin "8") (pinfunction "V+_8") (pintype "power_in"))
      (node (ref "U8") (pin "8") (pinfunction "V+_8") (pintype "power_in"))
      (node (ref "U9") (pin "8") (pinfunction "V+_8") (pintype "power_in"))
    )
    (net (code "17") (name "/CTEN") (class "Default")
      (node (ref "U12") (pin "4") (pinfunction "~{CTEN}_4") (pintype "passive"))
      (node (ref "U13") (pin "11") (pinfunction "4Y_11") (pintype "passive"))
    )
    (net (code "18") (name "/FREQ_SEL") (class "Default")
      (node (ref "C17") (pin "1") (pinfunction "1_1") (pintype "passive"))
      (node (ref "Q5") (pin "1") (pinfunction "G_1") (pintype "passive"))
      (node (ref "R45") (pin "2") (pinfunction "2_2") (pintype "passive"))
      (node (ref "U11") (pin "11") (pinfunction "4Y_11") (pintype "passive"))
    )
    (net (code "19") (name "/LED_PULSE_INV") (class "Default")
      (node (ref "U14") (pin "2") (pinfunction "IN1-_2") (pintype "tri_state"))
      (node (ref "U15") (pin "5") (pinfunction "1OUT_5") (pintype "passive"))
    )
    (net (code "20") (name "/LOAD_PULSE") (class "Default")
      (node (ref "U11") (pin "2") (pinfunction "1B_2") (pintype "passive"))
      (node (ref "U12") (pin "11") (pinfunction "~{LOAD}_11") (pintype "passive"))
      (node (ref "U8") (pin "7") (pinfunction "OUT2_7") (pintype "passive"))
    )
    (net (code "21") (name "/LOW_BAT") (class "Default")
      (node (ref "R11") (pin "2") (pinfunction "2_2") (pintype "passive"))
      (node (ref "R44") (pin "2") (pinfunction "2_2") (pintype "passive"))
      (node (ref "U7") (pin "7") (pinfunction "OUT2_7") (pintype "passive"))
    )
    (net (code "22") (name "/PWR_PULSE") (class "Default")
      (node (ref "R27") (pin "2") (pinfunction "2_2") (pintype "passive"))
      (node (ref "R35") (pin "2") (pinfunction "2_2") (pintype "passive"))
      (node (ref "U15") (pin "4") (pinfunction "1RESET_4") (pintype "passive"))
      (node (ref "U15") (pin "9") (pinfunction "2OUT_9") (pintype "passive"))
    )
    (net (code "23") (name "/SYS_5V") (class "Default")
      (node (ref "C22") (pin "2") (pinfunction "2_2") (pintype "passive"))
      (node (ref "C3") (pin "2") (pinfunction "A_2") (pintype "passive"))
      (node (ref "IR1") (pin "1") (pinfunction "A_1") (pintype "passive"))
      (node (ref "Q4") (pin "3") (pinfunction "D_3") (pintype "passive"))
      (node (ref "Q7") (pin "3") (pinfunction "D_3") (pintype "passive"))
      (node (ref "R3") (pin "2") (pinfunction "2_2") (pintype "passive"))
      (node (ref "R33") (pin "2") (pinfunction "2_2") (pintype "passive"))
      (node (ref "R34") (pin "2") (pinfunction "2_2") (pintype "passive"))
      (node (ref "R40") (pin "2") (pinfunction "2_2") (pintype "passive"))
      (node (ref "R41") (pin "1") (pinfunction "1_1") (pintype "passive"))
      (node (ref "U11") (pin "1") (pinfunction "1A_1") (pintype "passive"))
      (node (ref "U11") (pin "13") (pinfunction "4B_13") (pintype "passive"))
      (node (ref "U11") (pin "14") (pinfunction "VCC_14") (pintype "passive"))
      (node (ref "U11") (pin "5") (pinfunction "2B_5") (pintype "passive"))
      (node (ref "U12") (pin "16") (pinfunction "VCC_16") (pintype "passive"))
      (node (ref "U13") (pin "14") (pinfunction "VCC_14") (pintype "power_in"))
      (node (ref "U14") (pin "8") (pinfunction "V+_8") (pintype "power_in"))
      (node (ref "U15") (pin "10") (pinfunction "2RESET_10") (pintype "passive"))
      (node (ref "U15") (pin "14") (pinfunction "VDD_14") (pintype "power_in"))
      (node (ref "U2") (pin "3") (pinfunction "D_3") (pintype "passive"))
      (node (ref "U5") (pin "3") (pinfunction "D_3") (pintype "passive"))
    )
    (net (code "24") (name "/THRES") (class "Default")
      (node (ref "C21") (pin "1") (pinfunction "1_1") (pintype "passive"))
      (node (ref "R46") (pin "1") (pinfunction "1_1") (pintype "passive"))
      (node (ref "U15") (pin "2") (pinfunction "1THRES_2") (pintype "passive"))
      (node (ref "U15") (pin "6") (pinfunction "1TRIG_6") (pintype "passive"))
    )
    (net (code "25") (name "/V_REF") (class "Default")
      (node (ref "R14") (pin "1") (pinfunction "1_1") (pintype "passive"))
      (node (ref "R15") (pin "2") (pinfunction "2_2") (pintype "passive"))
      (node (ref "U7") (pin "2") (pinfunction "IN1-_2") (pintype "tri_state"))
      (node (ref "U7") (pin "6") (pinfunction "IN2-_6") (pintype "tri_state"))
    )
    (net (code "26") (name "GND") (class "Default")
      (node (ref "C1") (pin "1") (pinfunction "C_1") (pintype "passive"))
      (node (ref "C11") (pin "2") (pinfunction "2_2") (pintype "passive"))
      (node (ref "C12") (pin "2") (pinfunction "2_2") (pintype "passive"))
      (node (ref "C14") (pin "2") (pinfunction "2_2") (pintype "passive"))
      (node (ref "C15") (pin "2") (pinfunction "2_2") (pintype "passive"))
      (node (ref "C16") (pin "2") (pinfunction "2_2") (pintype "passive"))
      (node (ref "C17") (pin "2") (pinfunction "2_2") (pintype "passive"))
      (node (ref "C18") (pin "2") (pinfunction "2_2") (pintype "passive"))
      (node (ref "C19") (pin "1") (pinfunction "1_1") (pintype "passive"))
      (node (ref "C2") (pin "2") (pinfunction "2_2") (pintype "passive"))
      (node (ref "C20") (pin "2") (pinfunction "2_2") (pintype "passive"))
      (node (ref "C21") (pin "2") (pinfunction "2_2") (pintype "passive"))
      (node (ref "C22") (pin "1") (pinfunction "1_1") (pintype "passive"))
      (node (ref "C3") (pin "1") (pinfunction "C_1") (pintype "passive"))
      (node (ref "C5") (pin "2") (pinfunction "2_2") (pintype "passive"))
      (node (ref "C9") (pin "2") (pinfunction "2_2") (pintype "passive"))
      (node (ref "D1") (pin "1") (pinfunction "A_1") (pintype "passive"))
      (node (ref "D3") (pin "2") (pinfunction "A_2") (pintype "passive"))
      (node (ref "J2") (pin "2") (pinfunction "2_2") (pintype "passive"))
      (node (ref "LED2") (pin "1") (pinfunction "1_1") (pintype "passive"))
      (node (ref "Q1") (pin "2") (pinfunction "E_2") (pintype "passive"))
      (node (ref "Q2") (pin "2") (pinfunction "S_2") (pintype "passive"))
      (node (ref "R15") (pin "1") (pinfunction "1_1") (pintype "passive"))
      (node (ref "R2") (pin "2") (pinfunction "2_2") (pintype "passive"))
      (node (ref "R24") (pin "1") (pinfunction "1_1") (pintype "passive"))
      (node (ref "R26") (pin "1") (pinfunction "1_1") (pintype "passive"))
      (node (ref "R3") (pin "1") (pinfunction "1_1") (pintype "passive"))
      (node (ref "R31") (pin "1") (pinfunction "1_1") (pintype "passive"))
      (node (ref "R32") (pin "1") (pinfunction "1_1") (pintype "passive"))
      (node (ref "R36") (pin "1") (pinfunction "1_1") (pintype "passive"))
      (node (ref "R37") (pin "1") (pinfunction "1_1") (pintype "passive"))
      (node (ref "R45") (pin "1") (pinfunction "1_1") (pintype "passive"))
      (node (ref "R5") (pin "1") (pinfunction "1_1") (pintype "passive"))
      (node (ref "R7") (pin "2") (pinfunction "2_2") (pintype "passive"))
      (node (ref "R8") (pin "2") (pinfunction "2_2") (pintype "passive"))
      (node (ref "U10") (pin "4") (pinfunction "V-_4") (pintype "power_in"))
      (node (ref "U11") (pin "7") (pinfunction "GND_7") (pintype "passive"))
      (node (ref "U12") (pin "1") (pinfunction "B_1") (pintype "passive"))
      (node (ref "U12") (pin "10") (pinfunction "C_10") (pintype "passive"))
      (node (ref "U12") (pin "15") (pinfunction "A_15") (pintype "passive"))
      (node (ref "U12") (pin "5") (pinfunction "D/~{U}_5") (pintype "passive"))
      (node (ref "U12") (pin "8") (pinfunction "GND_8") (pintype "passive"))
      (node (ref "U12") (pin "9") (pinfunction "D_9") (pintype "passive"))
      (node (ref "U13") (pin "7") (pinfunction "GND_7") (pintype "power_in"))
      (node (ref "U14") (pin "4") (pinfunction "V-_4") (pintype "power_in"))
      (node (ref "U15") (pin "7") (pinfunction "GND_7") (pintype "power_in"))
      (node (ref "U3") (pin "VNEG") (pinfunction "-V_VNEG") (pintype "passive"))
      (node (ref "U6") (pin "3") (pinfunction "GND_3") (pintype "power_in"))
      (node (ref "U6") (pin "6") (pinfunction "GND_6") (pintype "power_in"))
      (node (ref "U6") (pin "7") (pinfunction "GND_7") (pintype "power_in"))
      (node (ref "U7") (pin "4") (pinfunction "V-_4") (pintype "power_in"))
      (node (ref "U8") (pin "4") (pinfunction "V-_4") (pintype "power_in"))
      (node (ref "U9") (pin "4") (pinfunction "V-_4") (pintype "power_in"))
    )
    (net (code "27") (name "Net-(C23-Pad2)") (class "Default")
      (node (ref "C23") (pin "2") (pinfunction "2_2") (pintype "passive"))
      (node (ref "R49") (pin "1") (pinfunction "1_1") (pintype "passive"))
      (node (ref "R50") (pin "1") (pinfunction "1_1") (pintype "passive"))
    )
    (net (code "28") (name "Net-(D1-K)") (class "Default")
      (node (ref "D1") (pin "3") (pinfunction "K_3") (pintype "passive"))
      (node (ref "R13") (pin "1") (pinfunction "1_1") (pintype "passive"))
      (node (ref "R14") (pin "2") (pinfunction "2_2") (pintype "passive"))
    )
    (net (code "29") (name "Net-(D2-A)") (class "Default")
      (node (ref "C6") (pin "2") (pinfunction "2_2") (pintype "passive"))
      (node (ref "D2") (pin "2") (pinfunction "A_2") (pintype "passive"))
      (node (ref "U8") (pin "1") (pinfunction "OUT1_1") (pintype "passive"))
    )
    (net (code "30") (name "Net-(D2-C)") (class "Default")
      (node (ref "D2") (pin "1") (pinfunction "C_1") (pintype "passive"))
      (node (ref "R19") (pin "2") (pinfunction "2_2") (pintype "passive"))
    )
    (net (code "31") (name "Net-(D3-C)") (class "Default")
      (node (ref "C8") (pin "2") (pinfunction "2_2") (pintype "passive"))
      (node (ref "D3") (pin "1") (pinfunction "C_1") (pintype "passive"))
      (node (ref "Q2") (pin "1") (pinfunction "G_1") (pintype "passive"))
      (node (ref "R26") (pin "2") (pinfunction "2_2") (pintype "passive"))
    )
    (net (code "32") (name "Net-(D4-A)") (class "Default")
      (node (ref "D4") (pin "2") (pinfunction "A_2") (pintype "passive"))
      (node (ref "R39") (pin "1") (pinfunction "1_1") (pintype "passive"))
      (node (ref "R40") (pin "1") (pinfunction "1_1") (pintype "passive"))
      (node (ref "R43") (pin "2") (pinfunction "2_2") (pintype "passive"))
      (node (ref "U15") (pin "13") (pinfunction "2DISCH_13") (pintype "passive"))
    )
    (net (code "33") (name "Net-(D4-C)") (class "Default")
      (node (ref "C20") (pin "1") (pinfunction "1_1") (pintype "passive"))
      (node (ref "D4") (pin "1") (pinfunction "C_1") (pintype "passive"))
      (node (ref "Q5") (pin "2") (pinfunction "S_2") (pintype "passive"))
      (node (ref "R43") (pin "1") (pinfunction "1_1") (pintype "passive"))
      (node (ref "U15") (pin "12") (pinfunction "2THRES_12") (pintype "passive"))
      (node (ref "U15") (pin "8") (pinfunction "2TRIG_8") (pintype "passive"))
    )
    (net (code "34") (name "Net-(D5-A)") (class "Default")
      (node (ref "D5") (pin "2") (pinfunction "A_2") (pintype "passive"))
      (node (ref "Q6") (pin "4") (pinfunction "D_4") (pintype "passive"))
    )
    (net (code "35") (name "Net-(D5-C)") (class "Default")
      (node (ref "D5") (pin "1") (pinfunction "C_1") (pintype "passive"))
      (node (ref "D6") (pin "1") (pinfunction "C_1") (pintype "passive"))
      (node (ref "R47") (pin "1") (pinfunction "1_1") (pintype "passive"))
    )
    (net (code "36") (name "Net-(IR1-K)") (class "Default")
      (node (ref "IR1") (pin "2") (pinfunction "K_2") (pintype "passive"))
      (node (ref "Q3") (pin "3") (pinfunction "D_3") (pintype "passive"))
    )
    (net (code "37") (name "Net-(LED1-Pad1)") (class "Default")
      (node (ref "LED1") (pin "1") (pinfunction "1_1") (pintype "passive"))
      (node (ref "R8") (pin "1") (pinfunction "1_1") (pintype "passive"))
    )
    (net (code "38") (name "Net-(LED2-Pad2)") (class "Default")
      (node (ref "LED2") (pin "2") (pinfunction "2_2") (pintype "passive"))
      (node (ref "R38") (pin "2") (pinfunction "2_2") (pintype "passive"))
    )
    (net (code "39") (name "Net-(Q2-D)") (class "Default")
      (node (ref "C6") (pin "1") (pinfunction "1_1") (pintype "passive"))
      (node (ref "Q2") (pin "3") (pinfunction "D_3") (pintype "passive"))
      (node (ref "U8") (pin "2") (pinfunction "IN1-_2") (pintype "tri_state"))
    )
    (net (code "40") (name "Net-(Q3-G)") (class "Default")
      (node (ref "Q3") (pin "1") (pinfunction "G_1") (pintype "passive"))
      (node (ref "R28") (pin "2") (pinfunction "2_2") (pintype "passive"))
    )
    (net (code "41") (name "Net-(Q3-S)") (class "Default")
      (node (ref "Q3") (pin "2") (pinfunction "S_2") (pintype "passive"))
      (node (ref "R30") (pin "2") (pinfunction "2_2") (pintype "passive"))
      (node (ref "R32") (pin "2") (pinfunction "2_2") (pintype "passive"))
    )
    (net (code "42") (name "Net-(Q4-G)") (class "Default")
      (node (ref "Q4") (pin "1") (pinfunction "G_1") (pintype "passive"))
      (node (ref "R35") (pin "1") (pinfunction "1_1") (pintype "passive"))
      (node (ref "R36") (pin "2") (pinfunction "2_2") (pintype "passive"))
    )
    (net (code "43") (name "Net-(Q5-D)") (class "Default")
      (node (ref "Q5") (pin "3") (pinfunction "D_3") (pintype "passive"))
      (node (ref "R39") (pin "2") (pinfunction "2_2") (pintype "passive"))
    )
    (net (code "44") (name "Net-(Q6-G)") (class "Default")
      (node (ref "Q6") (pin "1") (pinfunction "G_1") (pintype "passive"))
      (node (ref "R42") (pin "1") (pinfunction "1_1") (pintype "passive"))
      (node (ref "R44") (pin "1") (pinfunction "1_1") (pintype "passive"))
    )
    (net (code "45") (name "Net-(Q6-S)") (class "Default")
      (node (ref "Q6") (pin "3") (pinfunction "S_3") (pintype "passive"))
      (node (ref "R38") (pin "1") (pinfunction "1_1") (pintype "passive"))
      (node (ref "R42") (pin "2") (pinfunction "2_2") (pintype "passive"))
    )
    (net (code "46") (name "Net-(Q7-G)") (class "Default")
      (node (ref "C23") (pin "1") (pinfunction "1_1") (pintype "passive"))
      (node (ref "Q7") (pin "1") (pinfunction "G_1") (pintype "passive"))
      (node (ref "R47") (pin "2") (pinfunction "2_2") (pintype "passive"))
      (node (ref "R49") (pin "2") (pinfunction "2_2") (pintype "passive"))
    )
    (net (code "47") (name "Net-(Q7-S)") (class "Default")
      (node (ref "Q7") (pin "2") (pinfunction "S_2") (pintype "passive"))
      (node (ref "R50") (pin "2") (pinfunction "2_2") (pintype "passive"))
    )
    (net (code "48") (name "Net-(U8A-IN1+)") (class "Default")
      (node (ref "R16") (pin "1") (pinfunction "1_1") (pintype "passive"))
      (node (ref "U8") (pin "3") (pinfunction "IN1+_3") (pintype "tri_state"))
      (node (ref "U9") (pin "7") (pinfunction "OUT2_7") (pintype "passive"))
    )
    (net (code "49") (name "Net-(U8B-IN2+)") (class "Default")
      (node (ref "C15") (pin "1") (pinfunction "1_1") (pintype "passive"))
      (node (ref "R33") (pin "1") (pinfunction "1_1") (pintype "passive"))
      (node (ref "R34") (pin "1") (pinfunction "1_1") (pintype "passive"))
      (node (ref "R37") (pin "2") (pinfunction "2_2") (pintype "passive"))
      (node (ref "U8") (pin "5") (pinfunction "IN2+_5") (pintype "tri_state"))
      (node (ref "U8") (pin "6") (pinfunction "IN2-_6") (pintype "tri_state"))
    )
    (net (code "50") (name "Net-(U9A-IN1+)") (class "Default")
      (node (ref "R20") (pin "2") (pinfunction "2_2") (pintype "passive"))
      (node (ref "R23") (pin "1") (pinfunction "1_1") (pintype "passive"))
      (node (ref "U9") (pin "3") (pinfunction "IN1+_3") (pintype "tri_state"))
    )
    (net (code "51") (name "Net-(U9A-OUT1)") (class "Default")
      (node (ref "R18") (pin "1") (pinfunction "1_1") (pintype "passive"))
      (node (ref "R23") (pin "2") (pinfunction "2_2") (pintype "passive"))
      (node (ref "U9") (pin "1") (pinfunction "OUT1_1") (pintype "passive"))
    )
    (net (code "52") (name "Net-(U9B-IN2+)") (class "Default")
      (node (ref "C10") (pin "2") (pinfunction "2_2") (pintype "passive"))
      (node (ref "R16") (pin "2") (pinfunction "2_2") (pintype "passive"))
      (node (ref "R22") (pin "2") (pinfunction "2_2") (pintype "passive"))
      (node (ref "R25") (pin "2") (pinfunction "2_2") (pintype "passive"))
      (node (ref "U9") (pin "5") (pinfunction "IN2+_5") (pintype "tri_state"))
      (node (ref "U9") (pin "6") (pinfunction "IN2-_6") (pintype "tri_state"))
    )
    (net (code "53") (name "Net-(U10A-IN1+)") (class "Default")
      (node (ref "C12") (pin "1") (pinfunction "1_1") (pintype "passive"))
      (node (ref "R21") (pin "1") (pinfunction "1_1") (pintype "passive"))
      (node (ref "R22") (pin "1") (pinfunction "1_1") (pintype "passive"))
      (node (ref "R24") (pin "2") (pinfunction "2_2") (pintype "passive"))
      (node (ref "R25") (pin "1") (pinfunction "1_1") (pintype "passive"))
      (node (ref "U10") (pin "3") (pinfunction "IN1+_3") (pintype "tri_state"))
    )
    (net (code "54") (name "Net-(U10A-IN1-)") (class "Default")
      (node (ref "C7") (pin "1") (pinfunction "1_1") (pintype "passive"))
      (node (ref "R17") (pin "1") (pinfunction "1_1") (pintype "passive"))
      (node (ref "U10") (pin "2") (pinfunction "IN1-_2") (pintype "tri_state"))
    )
    (net (code "55") (name "Net-(U10A-OUT1)") (class "Default")
      (node (ref "C10") (pin "1") (pinfunction "1_1") (pintype "passive"))
      (node (ref "C7") (pin "2") (pinfunction "2_2") (pintype "passive"))
      (node (ref "R17") (pin "2") (pinfunction "2_2") (pintype "passive"))
      (node (ref "U10") (pin "1") (pinfunction "OUT1_1") (pintype "passive"))
    )
    (net (code "56") (name "Net-(U10B-IN2+)") (class "Default")
      (node (ref "C11") (pin "1") (pinfunction "1_1") (pintype "passive"))
      (node (ref "R19") (pin "1") (pinfunction "1_1") (pintype "passive"))
      (node (ref "U10") (pin "5") (pinfunction "IN2+_5") (pintype "tri_state"))
    )
    (net (code "57") (name "Net-(U10B-IN2-)") (class "Default")
      (node (ref "R20") (pin "1") (pinfunction "1_1") (pintype "passive"))
      (node (ref "U10") (pin "6") (pinfunction "IN2-_6") (pintype "tri_state"))
      (node (ref "U10") (pin "7") (pinfunction "OUT2_7") (pintype "passive"))
    )
    (net (code "58") (name "Net-(U11-1Y)") (class "Default")
      (node (ref "U11") (pin "3") (pinfunction "1Y_3") (pintype "passive"))
      (node (ref "U12") (pin "14") (pinfunction "CLK_14") (pintype "passive"))
    )
    (net (code "59") (name "Net-(U11-2A)") (class "Default")
      (node (ref "U11") (pin "4") (pinfunction "2A_4") (pintype "passive"))
      (node (ref "U13") (pin "3") (pinfunction "1Y_3") (pintype "passive"))
    )
    (net (code "60") (name "Net-(U11-2Y)") (class "Default")
      (node (ref "U11") (pin "6") (pinfunction "2Y_6") (pintype "passive"))
      (node (ref "U13") (pin "12") (pinfunction "4A_12") (pintype "passive"))
      (node (ref "U13") (pin "4") (pinfunction "2A_4") (pintype "passive"))
    )
    (net (code "61") (name "Net-(U11-3Y)") (class "Default")
      (node (ref "U11") (pin "8") (pinfunction "3Y_8") (pintype "passive"))
      (node (ref "U13") (pin "13") (pinfunction "4B_13") (pintype "passive"))
    )
    (net (code "62") (name "Net-(U11-4A)") (class "Default")
      (node (ref "U11") (pin "12") (pinfunction "4A_12") (pintype "passive"))
      (node (ref "U13") (pin "6") (pinfunction "2Y_6") (pintype "passive"))
    )
    (net (code "63") (name "Net-(U12-QA)") (class "Default")
      (node (ref "U12") (pin "3") (pinfunction "QA_3") (pintype "passive"))
      (node (ref "U13") (pin "1") (pinfunction "1A_1") (pintype "passive"))
    )
    (net (code "64") (name "Net-(U12-QB)") (class "Default")
      (node (ref "U12") (pin "2") (pinfunction "QB_2") (pintype "passive"))
      (node (ref "U13") (pin "2") (pinfunction "1B_2") (pintype "passive"))
    )
    (net (code "65") (name "Net-(U14A-IN1+)") (class "Default")
      (node (ref "R27") (pin "1") (pinfunction "1_1") (pintype "passive"))
      (node (ref "R31") (pin "2") (pinfunction "2_2") (pintype "passive"))
      (node (ref "U14") (pin "3") (pinfunction "IN1+_3") (pintype "tri_state"))
    )
    (net (code "66") (name "Net-(U14A-OUT1)") (class "Default")
      (node (ref "R29") (pin "1") (pinfunction "1_1") (pintype "passive"))
      (node (ref "U14") (pin "1") (pinfunction "OUT1_1") (pintype "passive"))
    )
    (net (code "67") (name "Net-(U14B-IN2+)") (class "Default")
      (node (ref "C14") (pin "1") (pinfunction "1_1") (pintype "passive"))
      (node (ref "R29") (pin "2") (pinfunction "2_2") (pintype "passive"))
      (node (ref "U14") (pin "5") (pinfunction "IN2+_5") (pintype "tri_state"))
    )
    (net (code "68") (name "Net-(U14B-IN2-)") (class "Default")
      (node (ref "C13") (pin "2") (pinfunction "2_2") (pintype "passive"))
      (node (ref "R30") (pin "1") (pinfunction "1_1") (pintype "passive"))
      (node (ref "U14") (pin "6") (pinfunction "IN2-_6") (pintype "tri_state"))
    )
    (net (code "69") (name "Net-(U14B-OUT2)") (class "Default")
      (node (ref "C13") (pin "1") (pinfunction "1_1") (pintype "passive"))
      (node (ref "R28") (pin "1") (pinfunction "1_1") (pintype "passive"))
      (node (ref "U14") (pin "7") (pinfunction "OUT2_7") (pintype "passive"))
    )
    (net (code "70") (name "Net-(U15-1CONT)") (class "Default")
      (node (ref "C18") (pin "1") (pinfunction "1_1") (pintype "passive"))
      (node (ref "U15") (pin "3") (pinfunction "1CONT_3") (pintype "passive"))
    )
    (net (code "71") (name "Net-(U15-1DISCH)") (class "Default")
      (node (ref "R41") (pin "2") (pinfunction "2_2") (pintype "passive"))
      (node (ref "R46") (pin "2") (pinfunction "2_2") (pintype "passive"))
      (node (ref "U15") (pin "1") (pinfunction "1DISCH_1") (pintype "passive"))
    )
    (net (code "72") (name "Net-(U15-2CONT)") (class "Default")
      (node (ref "C19") (pin "2") (pinfunction "2_2") (pintype "passive"))
      (node (ref "U15") (pin "11") (pinfunction "2CONT_11") (pintype "passive"))
    )
    (net (code "73") (name "unconnected-(D1-NC-Pad2)") (class "Default")
      (node (ref "D1") (pin "2") (pinfunction "NC_2") (pintype "passive"))
    )
    (net (code "74") (name "unconnected-(D6-A-Pad2)") (class "Default")
      (node (ref "D6") (pin "2") (pinfunction "A_2") (pintype "passive"))
    )
    (net (code "75") (name "unconnected-(U6-BYP-Pad4)") (class "Default")
      (node (ref "U6") (pin "4") (pinfunction "BYP_4") (pintype "passive"))
    )
    (net (code "76") (name "unconnected-(U9A-IN1--Pad2)") (class "Default")
      (node (ref "U9") (pin "2") (pinfunction "IN1-_2") (pintype "tri_state"))
    )
    (net (code "77") (name "unconnected-(U12-MAX{slash}MIN-Pad12)") (class "Default")
      (node (ref "U12") (pin "12") (pinfunction "MAX/MIN_12") (pintype "passive"))
    )
    (net (code "78") (name "unconnected-(U12-QD-Pad7)") (class "Default")
      (node (ref "U12") (pin "7") (pinfunction "QD_7") (pintype "passive"))
    )
    (net (code "79") (name "unconnected-(U12-~{RCO}-Pad13)") (class "Default")
      (node (ref "U12") (pin "13") (pinfunction "~{RCO}_13") (pintype "passive"))
    )
    (net (code "80") (name "unconnected-(U13-3A-Pad9)") (class "Default")
      (node (ref "U13") (pin "9") (pinfunction "3A_9") (pintype "passive"))
    )
    (net (code "81") (name "unconnected-(U13-3B-Pad10)") (class "Default")
      (node (ref "U13") (pin "10") (pinfunction "3B_10") (pintype "passive"))
    )
    (net (code "82") (name "unconnected-(U13-3Y-Pad8)") (class "Default")
      (node (ref "U13") (pin "8") (pinfunction "3Y_8") (pintype "passive"))
    )
  )
)
